# PGA257_socket.net
KiCad netlist of a schematic drawn in EAGLE
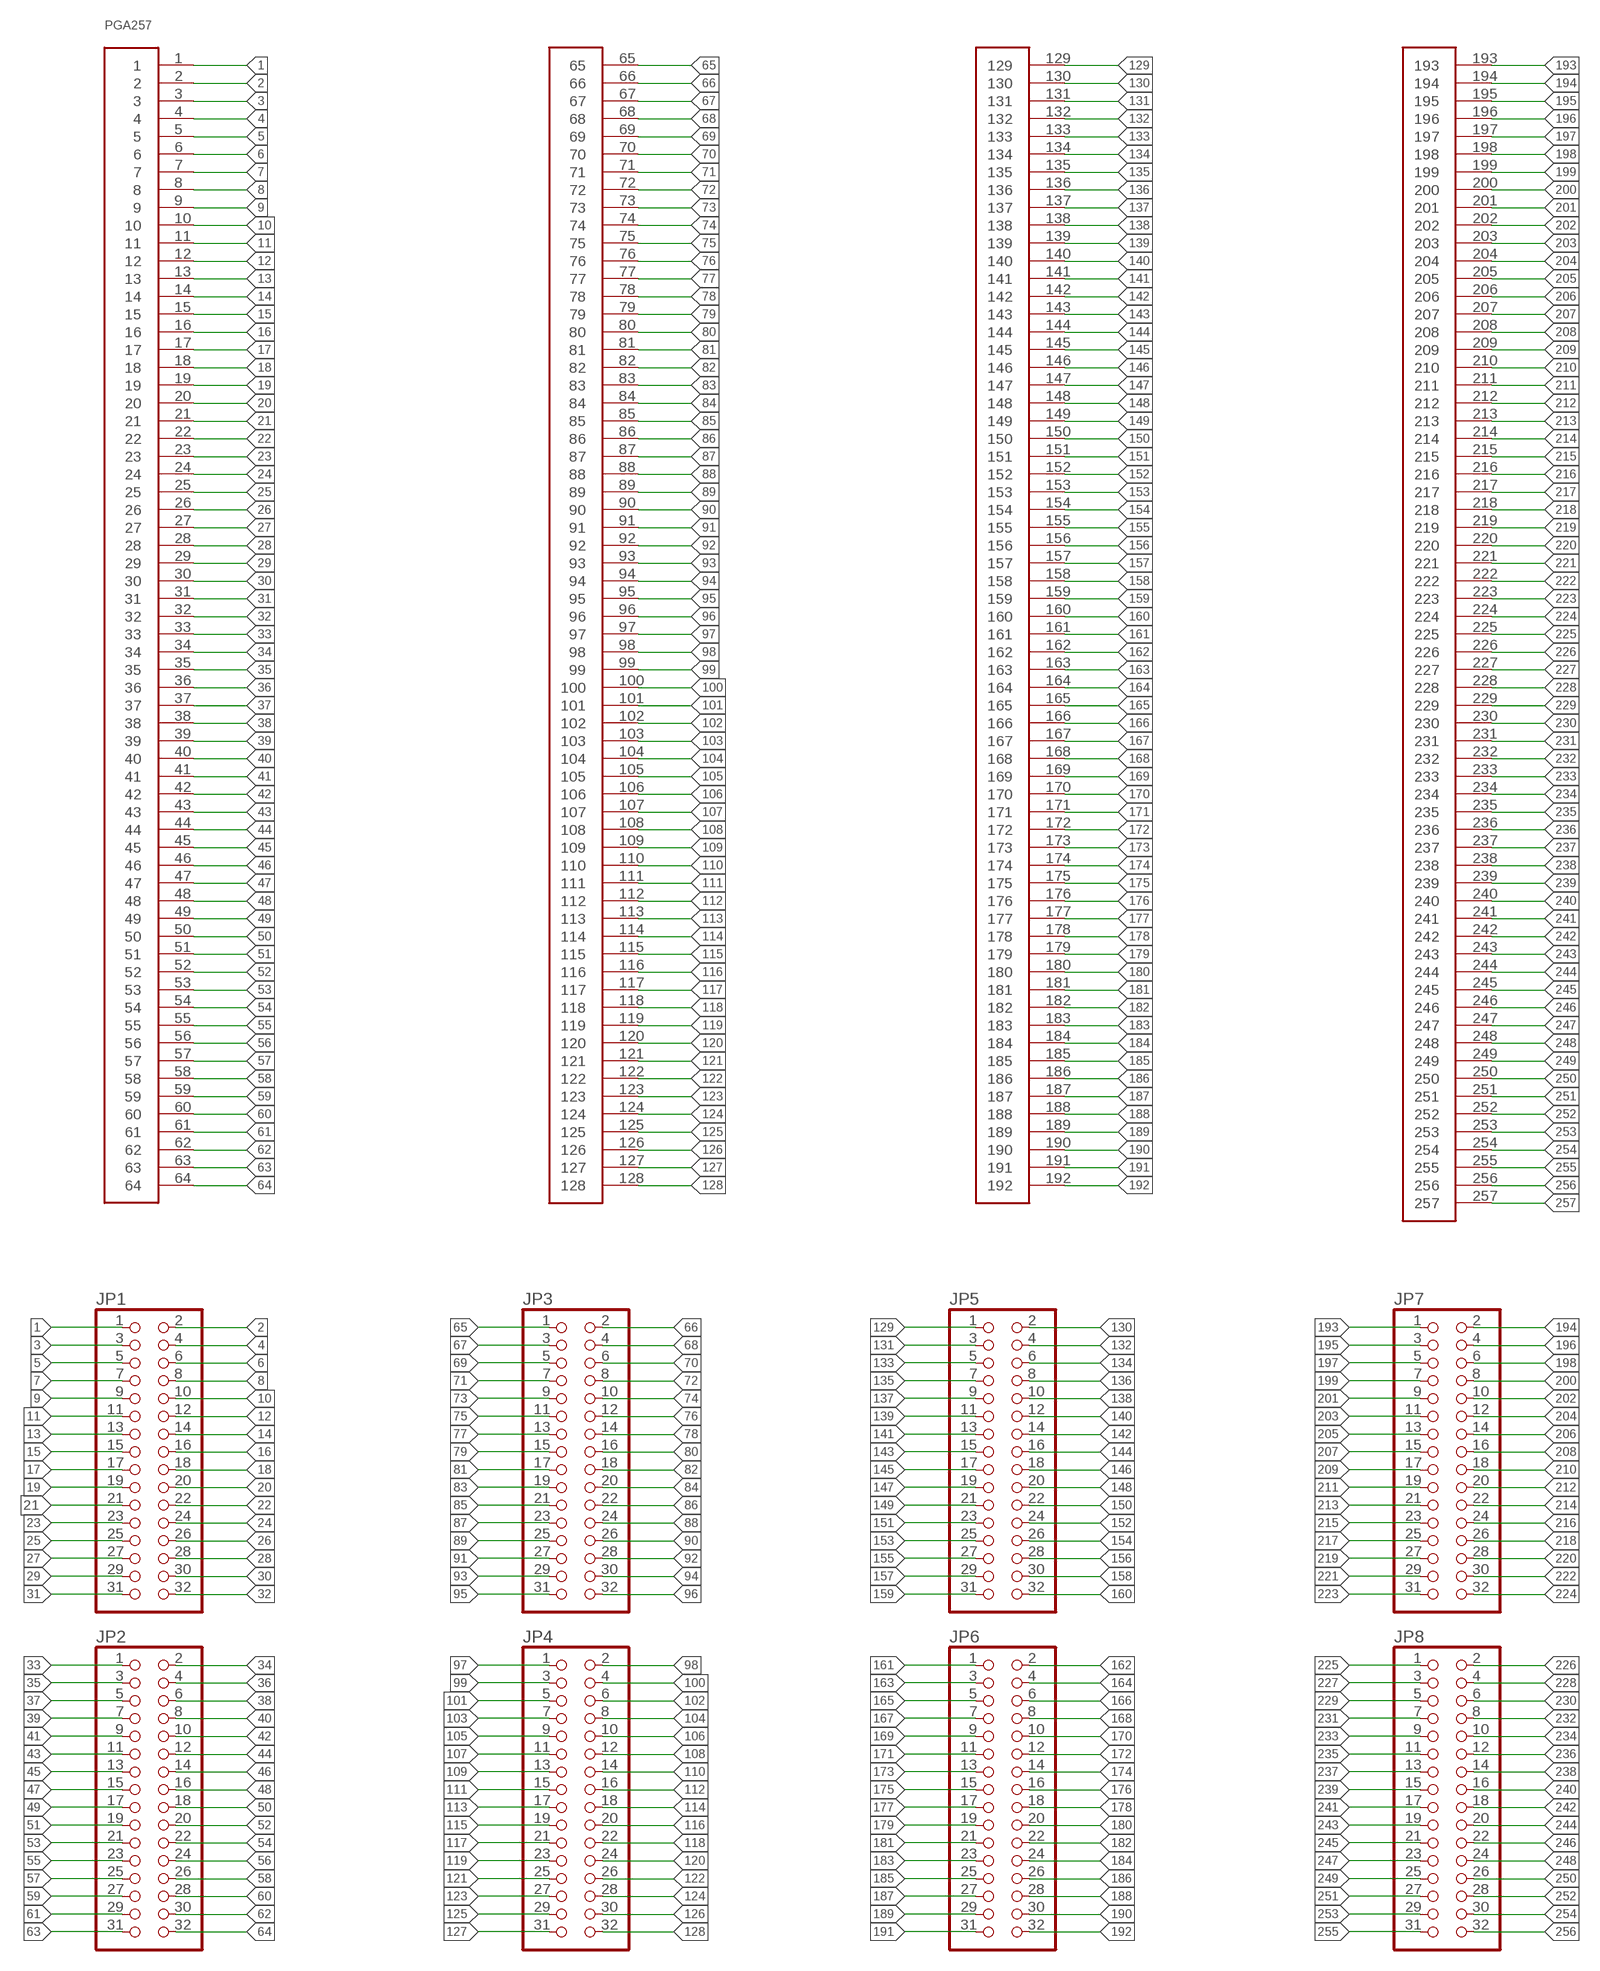
[diagram p0: schematic, sheet 1]

(export (version "E")
  (design (tool "Eeschema 10.0.6"))
  (components
    (comp (ref "JP1")
      (value "PINHD-2X16")
      (footprint "eagle-import:2X16")
      (libsource (lib "eagle-import") (part "PINHD-2X16"))
    )
    (comp (ref "JP2")
      (value "PINHD-2X16")
      (footprint "eagle-import:2X16")
      (libsource (lib "eagle-import") (part "PINHD-2X16"))
    )
    (comp (ref "JP3")
      (value "PINHD-2X16")
      (footprint "eagle-import:2X16")
      (libsource (lib "eagle-import") (part "PINHD-2X16"))
    )
    (comp (ref "JP4")
      (value "PINHD-2X16")
      (footprint "eagle-import:2X16")
      (libsource (lib "eagle-import") (part "PINHD-2X16"))
    )
    (comp (ref "JP5")
      (value "PINHD-2X16")
      (footprint "eagle-import:2X16")
      (libsource (lib "eagle-import") (part "PINHD-2X16"))
    )
    (comp (ref "JP6")
      (value "PINHD-2X16")
      (footprint "eagle-import:2X16")
      (libsource (lib "eagle-import") (part "PINHD-2X16"))
    )
    (comp (ref "JP7")
      (value "PINHD-2X16")
      (footprint "eagle-import:2X16")
      (libsource (lib "eagle-import") (part "PINHD-2X16"))
    )
    (comp (ref "JP8")
      (value "PINHD-2X16")
      (footprint "eagle-import:2X16")
      (libsource (lib "eagle-import") (part "PINHD-2X16"))
    )
    (comp (ref "PGA257")
      (value "PGA257")
      (footprint "eagle-import:PGA257")
      (libsource (lib "eagle-import") (part "PGA257"))
    )
  )
  (nets
    (net (code "1") (name "1") (class "Default")
      (node (ref "JP1") (pin "1") (pinfunction "1_1") (pintype "passive"))
      (node (ref "PGA257") (pin "1") (pinfunction "1_1") (pintype "bidirectional"))
    )
    (net (code "2") (name "2") (class "Default")
      (node (ref "JP1") (pin "2") (pinfunction "2_2") (pintype "passive"))
      (node (ref "PGA257") (pin "2") (pinfunction "2_2") (pintype "bidirectional"))
    )
    (net (code "3") (name "3") (class "Default")
      (node (ref "JP1") (pin "3") (pinfunction "3_3") (pintype "passive"))
      (node (ref "PGA257") (pin "3") (pinfunction "3_3") (pintype "bidirectional"))
    )
    (net (code "4") (name "4") (class "Default")
      (node (ref "JP1") (pin "4") (pinfunction "4_4") (pintype "passive"))
      (node (ref "PGA257") (pin "4") (pinfunction "4_4") (pintype "bidirectional"))
    )
    (net (code "5") (name "5") (class "Default")
      (node (ref "JP1") (pin "5") (pinfunction "5_5") (pintype "passive"))
      (node (ref "PGA257") (pin "5") (pinfunction "5_5") (pintype "bidirectional"))
    )
    (net (code "6") (name "6") (class "Default")
      (node (ref "JP1") (pin "6") (pinfunction "6_6") (pintype "passive"))
      (node (ref "PGA257") (pin "6") (pinfunction "6_6") (pintype "bidirectional"))
    )
    (net (code "7") (name "7") (class "Default")
      (node (ref "JP1") (pin "7") (pinfunction "7_7") (pintype "passive"))
      (node (ref "PGA257") (pin "7") (pinfunction "7_7") (pintype "bidirectional"))
    )
    (net (code "8") (name "8") (class "Default")
      (node (ref "JP1") (pin "8") (pinfunction "8_8") (pintype "passive"))
      (node (ref "PGA257") (pin "8") (pinfunction "8_8") (pintype "bidirectional"))
    )
    (net (code "9") (name "9") (class "Default")
      (node (ref "JP1") (pin "9") (pinfunction "9_9") (pintype "passive"))
      (node (ref "PGA257") (pin "9") (pinfunction "9_9") (pintype "bidirectional"))
    )
    (net (code "10") (name "10") (class "Default")
      (node (ref "JP1") (pin "10") (pinfunction "10_10") (pintype "passive"))
      (node (ref "PGA257") (pin "10") (pinfunction "10_10") (pintype "bidirectional"))
    )
    (net (code "11") (name "11") (class "Default")
      (node (ref "JP1") (pin "11") (pinfunction "11_11") (pintype "passive"))
      (node (ref "PGA257") (pin "11") (pinfunction "11_11") (pintype "bidirectional"))
    )
    (net (code "12") (name "12") (class "Default")
      (node (ref "JP1") (pin "12") (pinfunction "12_12") (pintype "passive"))
      (node (ref "PGA257") (pin "12") (pinfunction "12_12") (pintype "bidirectional"))
    )
    (net (code "13") (name "13") (class "Default")
      (node (ref "JP1") (pin "13") (pinfunction "13_13") (pintype "passive"))
      (node (ref "PGA257") (pin "13") (pinfunction "13_13") (pintype "bidirectional"))
    )
    (net (code "14") (name "14") (class "Default")
      (node (ref "JP1") (pin "14") (pinfunction "14_14") (pintype "passive"))
      (node (ref "PGA257") (pin "14") (pinfunction "14_14") (pintype "bidirectional"))
    )
    (net (code "15") (name "15") (class "Default")
      (node (ref "JP1") (pin "15") (pinfunction "15_15") (pintype "passive"))
      (node (ref "PGA257") (pin "15") (pinfunction "15_15") (pintype "bidirectional"))
    )
    (net (code "16") (name "16") (class "Default")
      (node (ref "JP1") (pin "16") (pinfunction "16_16") (pintype "passive"))
      (node (ref "PGA257") (pin "16") (pinfunction "16_16") (pintype "bidirectional"))
    )
    (net (code "17") (name "17") (class "Default")
      (node (ref "JP1") (pin "17") (pinfunction "17_17") (pintype "passive"))
      (node (ref "PGA257") (pin "17") (pinfunction "17_17") (pintype "bidirectional"))
    )
    (net (code "18") (name "18") (class "Default")
      (node (ref "JP1") (pin "18") (pinfunction "18_18") (pintype "passive"))
      (node (ref "PGA257") (pin "18") (pinfunction "18_18") (pintype "bidirectional"))
    )
    (net (code "19") (name "19") (class "Default")
      (node (ref "JP1") (pin "19") (pinfunction "19_19") (pintype "passive"))
      (node (ref "PGA257") (pin "19") (pinfunction "19_19") (pintype "bidirectional"))
    )
    (net (code "20") (name "20") (class "Default")
      (node (ref "JP1") (pin "20") (pinfunction "20_20") (pintype "passive"))
      (node (ref "PGA257") (pin "20") (pinfunction "20_20") (pintype "bidirectional"))
    )
    (net (code "21") (name "21") (class "Default")
      (node (ref "JP1") (pin "21") (pinfunction "21_21") (pintype "passive"))
      (node (ref "PGA257") (pin "21") (pinfunction "21_21") (pintype "bidirectional"))
    )
    (net (code "22") (name "22") (class "Default")
      (node (ref "JP1") (pin "22") (pinfunction "22_22") (pintype "passive"))
      (node (ref "PGA257") (pin "22") (pinfunction "22_22") (pintype "bidirectional"))
    )
    (net (code "23") (name "23") (class "Default")
      (node (ref "JP1") (pin "23") (pinfunction "23_23") (pintype "passive"))
      (node (ref "PGA257") (pin "23") (pinfunction "23_23") (pintype "bidirectional"))
    )
    (net (code "24") (name "24") (class "Default")
      (node (ref "JP1") (pin "24") (pinfunction "24_24") (pintype "passive"))
      (node (ref "PGA257") (pin "24") (pinfunction "24_24") (pintype "bidirectional"))
    )
    (net (code "25") (name "25") (class "Default")
      (node (ref "JP1") (pin "25") (pinfunction "25_25") (pintype "passive"))
      (node (ref "PGA257") (pin "25") (pinfunction "25_25") (pintype "bidirectional"))
    )
    (net (code "26") (name "26") (class "Default")
      (node (ref "JP1") (pin "26") (pinfunction "26_26") (pintype "passive"))
      (node (ref "PGA257") (pin "26") (pinfunction "26_26") (pintype "bidirectional"))
    )
    (net (code "27") (name "27") (class "Default")
      (node (ref "JP1") (pin "27") (pinfunction "27_27") (pintype "passive"))
      (node (ref "PGA257") (pin "27") (pinfunction "27_27") (pintype "bidirectional"))
    )
    (net (code "28") (name "28") (class "Default")
      (node (ref "JP1") (pin "28") (pinfunction "28_28") (pintype "passive"))
      (node (ref "PGA257") (pin "28") (pinfunction "28_28") (pintype "bidirectional"))
    )
    (net (code "29") (name "29") (class "Default")
      (node (ref "JP1") (pin "29") (pinfunction "29_29") (pintype "passive"))
      (node (ref "PGA257") (pin "29") (pinfunction "29_29") (pintype "bidirectional"))
    )
    (net (code "30") (name "30") (class "Default")
      (node (ref "JP1") (pin "30") (pinfunction "30_30") (pintype "passive"))
      (node (ref "PGA257") (pin "30") (pinfunction "30_30") (pintype "bidirectional"))
    )
    (net (code "31") (name "31") (class "Default")
      (node (ref "JP1") (pin "31") (pinfunction "31_31") (pintype "passive"))
      (node (ref "PGA257") (pin "31") (pinfunction "31_31") (pintype "bidirectional"))
    )
    (net (code "32") (name "32") (class "Default")
      (node (ref "JP1") (pin "32") (pinfunction "32_32") (pintype "passive"))
      (node (ref "PGA257") (pin "32") (pinfunction "32_32") (pintype "bidirectional"))
    )
    (net (code "33") (name "33") (class "Default")
      (node (ref "JP2") (pin "1") (pinfunction "1_1") (pintype "passive"))
      (node (ref "PGA257") (pin "33") (pinfunction "33_33") (pintype "bidirectional"))
    )
    (net (code "34") (name "34") (class "Default")
      (node (ref "JP2") (pin "2") (pinfunction "2_2") (pintype "passive"))
      (node (ref "PGA257") (pin "34") (pinfunction "34_34") (pintype "bidirectional"))
    )
    (net (code "35") (name "35") (class "Default")
      (node (ref "JP2") (pin "3") (pinfunction "3_3") (pintype "passive"))
      (node (ref "PGA257") (pin "35") (pinfunction "35_35") (pintype "bidirectional"))
    )
    (net (code "36") (name "36") (class "Default")
      (node (ref "JP2") (pin "4") (pinfunction "4_4") (pintype "passive"))
      (node (ref "PGA257") (pin "36") (pinfunction "36_36") (pintype "bidirectional"))
    )
    (net (code "37") (name "37") (class "Default")
      (node (ref "JP2") (pin "5") (pinfunction "5_5") (pintype "passive"))
      (node (ref "PGA257") (pin "37") (pinfunction "37_37") (pintype "bidirectional"))
    )
    (net (code "38") (name "38") (class "Default")
      (node (ref "JP2") (pin "6") (pinfunction "6_6") (pintype "passive"))
      (node (ref "PGA257") (pin "38") (pinfunction "38_38") (pintype "bidirectional"))
    )
    (net (code "39") (name "39") (class "Default")
      (node (ref "JP2") (pin "7") (pinfunction "7_7") (pintype "passive"))
      (node (ref "PGA257") (pin "39") (pinfunction "39_39") (pintype "bidirectional"))
    )
    (net (code "40") (name "40") (class "Default")
      (node (ref "JP2") (pin "8") (pinfunction "8_8") (pintype "passive"))
      (node (ref "PGA257") (pin "40") (pinfunction "40_40") (pintype "bidirectional"))
    )
    (net (code "41") (name "41") (class "Default")
      (node (ref "JP2") (pin "9") (pinfunction "9_9") (pintype "passive"))
      (node (ref "PGA257") (pin "41") (pinfunction "41_41") (pintype "bidirectional"))
    )
    (net (code "42") (name "42") (class "Default")
      (node (ref "JP2") (pin "10") (pinfunction "10_10") (pintype "passive"))
      (node (ref "PGA257") (pin "42") (pinfunction "42_42") (pintype "bidirectional"))
    )
    (net (code "43") (name "43") (class "Default")
      (node (ref "JP2") (pin "11") (pinfunction "11_11") (pintype "passive"))
      (node (ref "PGA257") (pin "43") (pinfunction "43_43") (pintype "bidirectional"))
    )
    (net (code "44") (name "44") (class "Default")
      (node (ref "JP2") (pin "12") (pinfunction "12_12") (pintype "passive"))
      (node (ref "PGA257") (pin "44") (pinfunction "44_44") (pintype "bidirectional"))
    )
    (net (code "45") (name "45") (class "Default")
      (node (ref "JP2") (pin "13") (pinfunction "13_13") (pintype "passive"))
      (node (ref "PGA257") (pin "45") (pinfunction "45_45") (pintype "bidirectional"))
    )
    (net (code "46") (name "46") (class "Default")
      (node (ref "JP2") (pin "14") (pinfunction "14_14") (pintype "passive"))
      (node (ref "PGA257") (pin "46") (pinfunction "46_46") (pintype "bidirectional"))
    )
    (net (code "47") (name "47") (class "Default")
      (node (ref "JP2") (pin "15") (pinfunction "15_15") (pintype "passive"))
      (node (ref "PGA257") (pin "47") (pinfunction "47_47") (pintype "bidirectional"))
    )
    (net (code "48") (name "48") (class "Default")
      (node (ref "JP2") (pin "16") (pinfunction "16_16") (pintype "passive"))
      (node (ref "PGA257") (pin "48") (pinfunction "48_48") (pintype "bidirectional"))
    )
    (net (code "49") (name "49") (class "Default")
      (node (ref "JP2") (pin "17") (pinfunction "17_17") (pintype "passive"))
      (node (ref "PGA257") (pin "49") (pinfunction "49_49") (pintype "bidirectional"))
    )
    (net (code "50") (name "50") (class "Default")
      (node (ref "JP2") (pin "18") (pinfunction "18_18") (pintype "passive"))
      (node (ref "PGA257") (pin "50") (pinfunction "50_50") (pintype "bidirectional"))
    )
    (net (code "51") (name "51") (class "Default")
      (node (ref "JP2") (pin "19") (pinfunction "19_19") (pintype "passive"))
      (node (ref "PGA257") (pin "51") (pinfunction "51_51") (pintype "bidirectional"))
    )
    (net (code "52") (name "52") (class "Default")
      (node (ref "JP2") (pin "20") (pinfunction "20_20") (pintype "passive"))
      (node (ref "PGA257") (pin "52") (pinfunction "52_52") (pintype "bidirectional"))
    )
    (net (code "53") (name "53") (class "Default")
      (node (ref "JP2") (pin "21") (pinfunction "21_21") (pintype "passive"))
      (node (ref "PGA257") (pin "53") (pinfunction "53_53") (pintype "bidirectional"))
    )
    (net (code "54") (name "54") (class "Default")
      (node (ref "JP2") (pin "22") (pinfunction "22_22") (pintype "passive"))
      (node (ref "PGA257") (pin "54") (pinfunction "54_54") (pintype "bidirectional"))
    )
    (net (code "55") (name "55") (class "Default")
      (node (ref "JP2") (pin "23") (pinfunction "23_23") (pintype "passive"))
      (node (ref "PGA257") (pin "55") (pinfunction "55_55") (pintype "bidirectional"))
    )
    (net (code "56") (name "56") (class "Default")
      (node (ref "JP2") (pin "24") (pinfunction "24_24") (pintype "passive"))
      (node (ref "PGA257") (pin "56") (pinfunction "56_56") (pintype "bidirectional"))
    )
    (net (code "57") (name "57") (class "Default")
      (node (ref "JP2") (pin "25") (pinfunction "25_25") (pintype "passive"))
      (node (ref "PGA257") (pin "57") (pinfunction "57_57") (pintype "bidirectional"))
    )
    (net (code "58") (name "58") (class "Default")
      (node (ref "JP2") (pin "26") (pinfunction "26_26") (pintype "passive"))
      (node (ref "PGA257") (pin "58") (pinfunction "58_58") (pintype "bidirectional"))
    )
    (net (code "59") (name "59") (class "Default")
      (node (ref "JP2") (pin "27") (pinfunction "27_27") (pintype "passive"))
      (node (ref "PGA257") (pin "59") (pinfunction "59_59") (pintype "bidirectional"))
    )
    (net (code "60") (name "60") (class "Default")
      (node (ref "JP2") (pin "28") (pinfunction "28_28") (pintype "passive"))
      (node (ref "PGA257") (pin "60") (pinfunction "60_60") (pintype "bidirectional"))
    )
    (net (code "61") (name "61") (class "Default")
      (node (ref "JP2") (pin "29") (pinfunction "29_29") (pintype "passive"))
      (node (ref "PGA257") (pin "61") (pinfunction "61_61") (pintype "bidirectional"))
    )
    (net (code "62") (name "62") (class "Default")
      (node (ref "JP2") (pin "30") (pinfunction "30_30") (pintype "passive"))
      (node (ref "PGA257") (pin "62") (pinfunction "62_62") (pintype "bidirectional"))
    )
    (net (code "63") (name "63") (class "Default")
      (node (ref "JP2") (pin "31") (pinfunction "31_31") (pintype "passive"))
      (node (ref "PGA257") (pin "63") (pinfunction "63_63") (pintype "bidirectional"))
    )
    (net (code "64") (name "64") (class "Default")
      (node (ref "JP2") (pin "32") (pinfunction "32_32") (pintype "passive"))
      (node (ref "PGA257") (pin "64") (pinfunction "64_64") (pintype "bidirectional"))
    )
    (net (code "65") (name "65") (class "Default")
      (node (ref "JP3") (pin "1") (pinfunction "1_1") (pintype "passive"))
      (node (ref "PGA257") (pin "65") (pinfunction "65_65") (pintype "bidirectional"))
    )
    (net (code "66") (name "66") (class "Default")
      (node (ref "JP3") (pin "2") (pinfunction "2_2") (pintype "passive"))
      (node (ref "PGA257") (pin "66") (pinfunction "66_66") (pintype "bidirectional"))
    )
    (net (code "67") (name "67") (class "Default")
      (node (ref "JP3") (pin "3") (pinfunction "3_3") (pintype "passive"))
      (node (ref "PGA257") (pin "67") (pinfunction "67_67") (pintype "bidirectional"))
    )
    (net (code "68") (name "68") (class "Default")
      (node (ref "JP3") (pin "4") (pinfunction "4_4") (pintype "passive"))
      (node (ref "PGA257") (pin "68") (pinfunction "68_68") (pintype "bidirectional"))
    )
    (net (code "69") (name "69") (class "Default")
      (node (ref "JP3") (pin "5") (pinfunction "5_5") (pintype "passive"))
      (node (ref "PGA257") (pin "69") (pinfunction "69_69") (pintype "bidirectional"))
    )
    (net (code "70") (name "70") (class "Default")
      (node (ref "JP3") (pin "6") (pinfunction "6_6") (pintype "passive"))
      (node (ref "PGA257") (pin "70") (pinfunction "70_70") (pintype "bidirectional"))
    )
    (net (code "71") (name "71") (class "Default")
      (node (ref "JP3") (pin "7") (pinfunction "7_7") (pintype "passive"))
      (node (ref "PGA257") (pin "71") (pinfunction "71_71") (pintype "bidirectional"))
    )
    (net (code "72") (name "72") (class "Default")
      (node (ref "JP3") (pin "8") (pinfunction "8_8") (pintype "passive"))
      (node (ref "PGA257") (pin "72") (pinfunction "72_72") (pintype "bidirectional"))
    )
    (net (code "73") (name "73") (class "Default")
      (node (ref "JP3") (pin "9") (pinfunction "9_9") (pintype "passive"))
      (node (ref "PGA257") (pin "73") (pinfunction "73_73") (pintype "bidirectional"))
    )
    (net (code "74") (name "74") (class "Default")
      (node (ref "JP3") (pin "10") (pinfunction "10_10") (pintype "passive"))
      (node (ref "PGA257") (pin "74") (pinfunction "74_74") (pintype "bidirectional"))
    )
    (net (code "75") (name "75") (class "Default")
      (node (ref "JP3") (pin "11") (pinfunction "11_11") (pintype "passive"))
      (node (ref "PGA257") (pin "75") (pinfunction "75_75") (pintype "bidirectional"))
    )
    (net (code "76") (name "76") (class "Default")
      (node (ref "JP3") (pin "12") (pinfunction "12_12") (pintype "passive"))
      (node (ref "PGA257") (pin "76") (pinfunction "76_76") (pintype "bidirectional"))
    )
    (net (code "77") (name "77") (class "Default")
      (node (ref "JP3") (pin "13") (pinfunction "13_13") (pintype "passive"))
      (node (ref "PGA257") (pin "77") (pinfunction "77_77") (pintype "bidirectional"))
    )
    (net (code "78") (name "78") (class "Default")
      (node (ref "JP3") (pin "14") (pinfunction "14_14") (pintype "passive"))
      (node (ref "PGA257") (pin "78") (pinfunction "78_78") (pintype "bidirectional"))
    )
    (net (code "79") (name "79") (class "Default")
      (node (ref "JP3") (pin "15") (pinfunction "15_15") (pintype "passive"))
      (node (ref "PGA257") (pin "79") (pinfunction "79_79") (pintype "bidirectional"))
    )
    (net (code "80") (name "80") (class "Default")
      (node (ref "JP3") (pin "16") (pinfunction "16_16") (pintype "passive"))
      (node (ref "PGA257") (pin "80") (pinfunction "80_80") (pintype "bidirectional"))
    )
    (net (code "81") (name "81") (class "Default")
      (node (ref "JP3") (pin "17") (pinfunction "17_17") (pintype "passive"))
      (node (ref "PGA257") (pin "81") (pinfunction "81_81") (pintype "bidirectional"))
    )
    (net (code "82") (name "82") (class "Default")
      (node (ref "JP3") (pin "18") (pinfunction "18_18") (pintype "passive"))
      (node (ref "PGA257") (pin "82") (pinfunction "82_82") (pintype "bidirectional"))
    )
    (net (code "83") (name "83") (class "Default")
      (node (ref "JP3") (pin "19") (pinfunction "19_19") (pintype "passive"))
      (node (ref "PGA257") (pin "83") (pinfunction "83_83") (pintype "bidirectional"))
    )
    (net (code "84") (name "84") (class "Default")
      (node (ref "JP3") (pin "20") (pinfunction "20_20") (pintype "passive"))
      (node (ref "PGA257") (pin "84") (pinfunction "84_84") (pintype "bidirectional"))
    )
    (net (code "85") (name "85") (class "Default")
      (node (ref "JP3") (pin "21") (pinfunction "21_21") (pintype "passive"))
      (node (ref "PGA257") (pin "85") (pinfunction "85_85") (pintype "bidirectional"))
    )
    (net (code "86") (name "86") (class "Default")
      (node (ref "JP3") (pin "22") (pinfunction "22_22") (pintype "passive"))
      (node (ref "PGA257") (pin "86") (pinfunction "86_86") (pintype "bidirectional"))
    )
    (net (code "87") (name "87") (class "Default")
      (node (ref "JP3") (pin "23") (pinfunction "23_23") (pintype "passive"))
      (node (ref "PGA257") (pin "87") (pinfunction "87_87") (pintype "bidirectional"))
    )
    (net (code "88") (name "88") (class "Default")
      (node (ref "JP3") (pin "24") (pinfunction "24_24") (pintype "passive"))
      (node (ref "PGA257") (pin "88") (pinfunction "88_88") (pintype "bidirectional"))
    )
    (net (code "89") (name "89") (class "Default")
      (node (ref "JP3") (pin "25") (pinfunction "25_25") (pintype "passive"))
      (node (ref "PGA257") (pin "89") (pinfunction "89_89") (pintype "bidirectional"))
    )
    (net (code "90") (name "90") (class "Default")
      (node (ref "JP3") (pin "26") (pinfunction "26_26") (pintype "passive"))
      (node (ref "PGA257") (pin "90") (pinfunction "90_90") (pintype "bidirectional"))
    )
    (net (code "91") (name "91") (class "Default")
      (node (ref "JP3") (pin "27") (pinfunction "27_27") (pintype "passive"))
      (node (ref "PGA257") (pin "91") (pinfunction "91_91") (pintype "bidirectional"))
    )
    (net (code "92") (name "92") (class "Default")
      (node (ref "JP3") (pin "28") (pinfunction "28_28") (pintype "passive"))
      (node (ref "PGA257") (pin "92") (pinfunction "92_92") (pintype "bidirectional"))
    )
    (net (code "93") (name "93") (class "Default")
      (node (ref "JP3") (pin "29") (pinfunction "29_29") (pintype "passive"))
      (node (ref "PGA257") (pin "93") (pinfunction "93_93") (pintype "bidirectional"))
    )
    (net (code "94") (name "94") (class "Default")
      (node (ref "JP3") (pin "30") (pinfunction "30_30") (pintype "passive"))
      (node (ref "PGA257") (pin "94") (pinfunction "94_94") (pintype "bidirectional"))
    )
    (net (code "95") (name "95") (class "Default")
      (node (ref "JP3") (pin "31") (pinfunction "31_31") (pintype "passive"))
      (node (ref "PGA257") (pin "95") (pinfunction "95_95") (pintype "bidirectional"))
    )
    (net (code "96") (name "96") (class "Default")
      (node (ref "JP3") (pin "32") (pinfunction "32_32") (pintype "passive"))
      (node (ref "PGA257") (pin "96") (pinfunction "96_96") (pintype "bidirectional"))
    )
    (net (code "97") (name "97") (class "Default")
      (node (ref "JP4") (pin "1") (pinfunction "1_1") (pintype "passive"))
      (node (ref "PGA257") (pin "97") (pinfunction "97_97") (pintype "bidirectional"))
    )
    (net (code "98") (name "98") (class "Default")
      (node (ref "JP4") (pin "2") (pinfunction "2_2") (pintype "passive"))
      (node (ref "PGA257") (pin "98") (pinfunction "98_98") (pintype "bidirectional"))
    )
    (net (code "99") (name "99") (class "Default")
      (node (ref "JP4") (pin "3") (pinfunction "3_3") (pintype "passive"))
      (node (ref "PGA257") (pin "99") (pinfunction "99_99") (pintype "bidirectional"))
    )
    (net (code "100") (name "100") (class "Default")
      (node (ref "JP4") (pin "4") (pinfunction "4_4") (pintype "passive"))
      (node (ref "PGA257") (pin "100") (pinfunction "100_100") (pintype "bidirectional"))
    )
    (net (code "101") (name "101") (class "Default")
      (node (ref "JP4") (pin "5") (pinfunction "5_5") (pintype "passive"))
      (node (ref "PGA257") (pin "101") (pinfunction "101_101") (pintype "bidirectional"))
    )
    (net (code "102") (name "102") (class "Default")
      (node (ref "JP4") (pin "6") (pinfunction "6_6") (pintype "passive"))
      (node (ref "PGA257") (pin "102") (pinfunction "102_102") (pintype "bidirectional"))
    )
    (net (code "103") (name "103") (class "Default")
      (node (ref "JP4") (pin "7") (pinfunction "7_7") (pintype "passive"))
      (node (ref "PGA257") (pin "103") (pinfunction "103_103") (pintype "bidirectional"))
    )
    (net (code "104") (name "104") (class "Default")
      (node (ref "JP4") (pin "8") (pinfunction "8_8") (pintype "passive"))
      (node (ref "PGA257") (pin "104") (pinfunction "104_104") (pintype "bidirectional"))
    )
    (net (code "105") (name "105") (class "Default")
      (node (ref "JP4") (pin "9") (pinfunction "9_9") (pintype "passive"))
      (node (ref "PGA257") (pin "105") (pinfunction "105_105") (pintype "bidirectional"))
    )
    (net (code "106") (name "106") (class "Default")
      (node (ref "JP4") (pin "10") (pinfunction "10_10") (pintype "passive"))
      (node (ref "PGA257") (pin "106") (pinfunction "106_106") (pintype "bidirectional"))
    )
    (net (code "107") (name "107") (class "Default")
      (node (ref "JP4") (pin "11") (pinfunction "11_11") (pintype "passive"))
      (node (ref "PGA257") (pin "107") (pinfunction "107_107") (pintype "bidirectional"))
    )
    (net (code "108") (name "108") (class "Default")
      (node (ref "JP4") (pin "12") (pinfunction "12_12") (pintype "passive"))
      (node (ref "PGA257") (pin "108") (pinfunction "108_108") (pintype "bidirectional"))
    )
    (net (code "109") (name "109") (class "Default")
      (node (ref "JP4") (pin "13") (pinfunction "13_13") (pintype "passive"))
      (node (ref "PGA257") (pin "109") (pinfunction "109_109") (pintype "bidirectional"))
    )
    (net (code "110") (name "110") (class "Default")
      (node (ref "JP4") (pin "14") (pinfunction "14_14") (pintype "passive"))
      (node (ref "PGA257") (pin "110") (pinfunction "110_110") (pintype "bidirectional"))
    )
    (net (code "111") (name "111") (class "Default")
      (node (ref "JP4") (pin "15") (pinfunction "15_15") (pintype "passive"))
      (node (ref "PGA257") (pin "111") (pinfunction "111_111") (pintype "bidirectional"))
    )
    (net (code "112") (name "112") (class "Default")
      (node (ref "JP4") (pin "16") (pinfunction "16_16") (pintype "passive"))
      (node (ref "PGA257") (pin "112") (pinfunction "112_112") (pintype "bidirectional"))
    )
    (net (code "113") (name "113") (class "Default")
      (node (ref "JP4") (pin "17") (pinfunction "17_17") (pintype "passive"))
      (node (ref "PGA257") (pin "113") (pinfunction "113_113") (pintype "bidirectional"))
    )
    (net (code "114") (name "114") (class "Default")
      (node (ref "JP4") (pin "18") (pinfunction "18_18") (pintype "passive"))
      (node (ref "PGA257") (pin "114") (pinfunction "114_114") (pintype "bidirectional"))
    )
    (net (code "115") (name "115") (class "Default")
      (node (ref "JP4") (pin "19") (pinfunction "19_19") (pintype "passive"))
      (node (ref "PGA257") (pin "115") (pinfunction "115_115") (pintype "bidirectional"))
    )
    (net (code "116") (name "116") (class "Default")
      (node (ref "JP4") (pin "20") (pinfunction "20_20") (pintype "passive"))
      (node (ref "PGA257") (pin "116") (pinfunction "116_116") (pintype "bidirectional"))
    )
    (net (code "117") (name "117") (class "Default")
      (node (ref "JP4") (pin "21") (pinfunction "21_21") (pintype "passive"))
      (node (ref "PGA257") (pin "117") (pinfunction "117_117") (pintype "bidirectional"))
    )
    (net (code "118") (name "118") (class "Default")
      (node (ref "JP4") (pin "22") (pinfunction "22_22") (pintype "passive"))
      (node (ref "PGA257") (pin "118") (pinfunction "118_118") (pintype "bidirectional"))
    )
    (net (code "119") (name "119") (class "Default")
      (node (ref "JP4") (pin "23") (pinfunction "23_23") (pintype "passive"))
      (node (ref "PGA257") (pin "119") (pinfunction "119_119") (pintype "bidirectional"))
    )
    (net (code "120") (name "120") (class "Default")
      (node (ref "JP4") (pin "24") (pinfunction "24_24") (pintype "passive"))
      (node (ref "PGA257") (pin "120") (pinfunction "120_120") (pintype "bidirectional"))
    )
    (net (code "121") (name "121") (class "Default")
      (node (ref "JP4") (pin "25") (pinfunction "25_25") (pintype "passive"))
      (node (ref "PGA257") (pin "121") (pinfunction "121_121") (pintype "bidirectional"))
    )
    (net (code "122") (name "122") (class "Default")
      (node (ref "JP4") (pin "26") (pinfunction "26_26") (pintype "passive"))
      (node (ref "PGA257") (pin "122") (pinfunction "122_122") (pintype "bidirectional"))
    )
    (net (code "123") (name "123") (class "Default")
      (node (ref "JP4") (pin "27") (pinfunction "27_27") (pintype "passive"))
      (node (ref "PGA257") (pin "123") (pinfunction "123_123") (pintype "bidirectional"))
    )
    (net (code "124") (name "124") (class "Default")
      (node (ref "JP4") (pin "28") (pinfunction "28_28") (pintype "passive"))
      (node (ref "PGA257") (pin "124") (pinfunction "124_124") (pintype "bidirectional"))
    )
    (net (code "125") (name "125") (class "Default")
      (node (ref "JP4") (pin "29") (pinfunction "29_29") (pintype "passive"))
      (node (ref "PGA257") (pin "125") (pinfunction "125_125") (pintype "bidirectional"))
    )
    (net (code "126") (name "126") (class "Default")
      (node (ref "JP4") (pin "30") (pinfunction "30_30") (pintype "passive"))
      (node (ref "PGA257") (pin "126") (pinfunction "126_126") (pintype "bidirectional"))
    )
    (net (code "127") (name "127") (class "Default")
      (node (ref "JP4") (pin "31") (pinfunction "31_31") (pintype "passive"))
      (node (ref "PGA257") (pin "127") (pinfunction "127_127") (pintype "bidirectional"))
    )
    (net (code "128") (name "128") (class "Default")
      (node (ref "JP4") (pin "32") (pinfunction "32_32") (pintype "passive"))
      (node (ref "PGA257") (pin "128") (pinfunction "128_128") (pintype "bidirectional"))
    )
    (net (code "129") (name "129") (class "Default")
      (node (ref "JP5") (pin "1") (pinfunction "1_1") (pintype "passive"))
      (node (ref "PGA257") (pin "129") (pinfunction "129_129") (pintype "bidirectional"))
    )
    (net (code "130") (name "130") (class "Default")
      (node (ref "JP5") (pin "2") (pinfunction "2_2") (pintype "passive"))
      (node (ref "PGA257") (pin "130") (pinfunction "130_130") (pintype "bidirectional"))
    )
    (net (code "131") (name "131") (class "Default")
      (node (ref "JP5") (pin "3") (pinfunction "3_3") (pintype "passive"))
      (node (ref "PGA257") (pin "131") (pinfunction "131_131") (pintype "bidirectional"))
    )
    (net (code "132") (name "132") (class "Default")
      (node (ref "JP5") (pin "4") (pinfunction "4_4") (pintype "passive"))
      (node (ref "PGA257") (pin "132") (pinfunction "132_132") (pintype "bidirectional"))
    )
    (net (code "133") (name "133") (class "Default")
      (node (ref "JP5") (pin "5") (pinfunction "5_5") (pintype "passive"))
      (node (ref "PGA257") (pin "133") (pinfunction "133_133") (pintype "bidirectional"))
    )
    (net (code "134") (name "134") (class "Default")
      (node (ref "JP5") (pin "6") (pinfunction "6_6") (pintype "passive"))
      (node (ref "PGA257") (pin "134") (pinfunction "134_134") (pintype "bidirectional"))
    )
    (net (code "135") (name "135") (class "Default")
      (node (ref "JP5") (pin "7") (pinfunction "7_7") (pintype "passive"))
      (node (ref "PGA257") (pin "135") (pinfunction "135_135") (pintype "bidirectional"))
    )
    (net (code "136") (name "136") (class "Default")
      (node (ref "JP5") (pin "8") (pinfunction "8_8") (pintype "passive"))
      (node (ref "PGA257") (pin "136") (pinfunction "136_136") (pintype "bidirectional"))
    )
    (net (code "137") (name "137") (class "Default")
      (node (ref "JP5") (pin "9") (pinfunction "9_9") (pintype "passive"))
      (node (ref "PGA257") (pin "137") (pinfunction "137_137") (pintype "bidirectional"))
    )
    (net (code "138") (name "138") (class "Default")
      (node (ref "JP5") (pin "10") (pinfunction "10_10") (pintype "passive"))
      (node (ref "PGA257") (pin "138") (pinfunction "138_138") (pintype "bidirectional"))
    )
    (net (code "139") (name "139") (class "Default")
      (node (ref "JP5") (pin "11") (pinfunction "11_11") (pintype "passive"))
      (node (ref "PGA257") (pin "139") (pinfunction "139_139") (pintype "bidirectional"))
    )
    (net (code "140") (name "140") (class "Default")
      (node (ref "JP5") (pin "12") (pinfunction "12_12") (pintype "passive"))
      (node (ref "PGA257") (pin "140") (pinfunction "140_140") (pintype "bidirectional"))
    )
    (net (code "141") (name "141") (class "Default")
      (node (ref "JP5") (pin "13") (pinfunction "13_13") (pintype "passive"))
      (node (ref "PGA257") (pin "141") (pinfunction "141_141") (pintype "bidirectional"))
    )
    (net (code "142") (name "142") (class "Default")
      (node (ref "JP5") (pin "14") (pinfunction "14_14") (pintype "passive"))
      (node (ref "PGA257") (pin "142") (pinfunction "142_142") (pintype "bidirectional"))
    )
    (net (code "143") (name "143") (class "Default")
      (node (ref "JP5") (pin "15") (pinfunction "15_15") (pintype "passive"))
      (node (ref "PGA257") (pin "143") (pinfunction "143_143") (pintype "bidirectional"))
    )
    (net (code "144") (name "144") (class "Default")
      (node (ref "JP5") (pin "16") (pinfunction "16_16") (pintype "passive"))
      (node (ref "PGA257") (pin "144") (pinfunction "144_144") (pintype "bidirectional"))
    )
    (net (code "145") (name "145") (class "Default")
      (node (ref "JP5") (pin "17") (pinfunction "17_17") (pintype "passive"))
      (node (ref "PGA257") (pin "145") (pinfunction "145_145") (pintype "bidirectional"))
    )
    (net (code "146") (name "146") (class "Default")
      (node (ref "JP5") (pin "18") (pinfunction "18_18") (pintype "passive"))
      (node (ref "PGA257") (pin "146") (pinfunction "146_146") (pintype "bidirectional"))
    )
    (net (code "147") (name "147") (class "Default")
      (node (ref "JP5") (pin "19") (pinfunction "19_19") (pintype "passive"))
      (node (ref "PGA257") (pin "147") (pinfunction "147_147") (pintype "bidirectional"))
    )
    (net (code "148") (name "148") (class "Default")
      (node (ref "JP5") (pin "20") (pinfunction "20_20") (pintype "passive"))
      (node (ref "PGA257") (pin "148") (pinfunction "148_148") (pintype "bidirectional"))
    )
    (net (code "149") (name "149") (class "Default")
      (node (ref "JP5") (pin "21") (pinfunction "21_21") (pintype "passive"))
      (node (ref "PGA257") (pin "149") (pinfunction "149_149") (pintype "bidirectional"))
    )
    (net (code "150") (name "150") (class "Default")
      (node (ref "JP5") (pin "22") (pinfunction "22_22") (pintype "passive"))
      (node (ref "PGA257") (pin "150") (pinfunction "150_150") (pintype "bidirectional"))
    )
    (net (code "151") (name "151") (class "Default")
      (node (ref "JP5") (pin "23") (pinfunction "23_23") (pintype "passive"))
      (node (ref "PGA257") (pin "151") (pinfunction "151_151") (pintype "bidirectional"))
    )
    (net (code "152") (name "152") (class "Default")
      (node (ref "JP5") (pin "24") (pinfunction "24_24") (pintype "passive"))
      (node (ref "PGA257") (pin "152") (pinfunction "152_152") (pintype "bidirectional"))
    )
    (net (code "153") (name "153") (class "Default")
      (node (ref "JP5") (pin "25") (pinfunction "25_25") (pintype "passive"))
      (node (ref "PGA257") (pin "153") (pinfunction "153_153") (pintype "bidirectional"))
    )
    (net (code "154") (name "154") (class "Default")
      (node (ref "JP5") (pin "26") (pinfunction "26_26") (pintype "passive"))
      (node (ref "PGA257") (pin "154") (pinfunction "154_154") (pintype "bidirectional"))
    )
    (net (code "155") (name "155") (class "Default")
      (node (ref "JP5") (pin "27") (pinfunction "27_27") (pintype "passive"))
      (node (ref "PGA257") (pin "155") (pinfunction "155_155") (pintype "bidirectional"))
    )
    (net (code "156") (name "156") (class "Default")
      (node (ref "JP5") (pin "28") (pinfunction "28_28") (pintype "passive"))
      (node (ref "PGA257") (pin "156") (pinfunction "156_156") (pintype "bidirectional"))
    )
    (net (code "157") (name "157") (class "Default")
      (node (ref "JP5") (pin "29") (pinfunction "29_29") (pintype "passive"))
      (node (ref "PGA257") (pin "157") (pinfunction "157_157") (pintype "bidirectional"))
    )
    (net (code "158") (name "158") (class "Default")
      (node (ref "JP5") (pin "30") (pinfunction "30_30") (pintype "passive"))
      (node (ref "PGA257") (pin "158") (pinfunction "158_158") (pintype "bidirectional"))
    )
    (net (code "159") (name "159") (class "Default")
      (node (ref "JP5") (pin "31") (pinfunction "31_31") (pintype "passive"))
      (node (ref "PGA257") (pin "159") (pinfunction "159_159") (pintype "bidirectional"))
    )
    (net (code "160") (name "160") (class "Default")
      (node (ref "JP5") (pin "32") (pinfunction "32_32") (pintype "passive"))
      (node (ref "PGA257") (pin "160") (pinfunction "160_160") (pintype "bidirectional"))
    )
    (net (code "161") (name "161") (class "Default")
      (node (ref "JP6") (pin "1") (pinfunction "1_1") (pintype "passive"))
      (node (ref "PGA257") (pin "161") (pinfunction "161_161") (pintype "bidirectional"))
    )
    (net (code "162") (name "162") (class "Default")
      (node (ref "JP6") (pin "2") (pinfunction "2_2") (pintype "passive"))
      (node (ref "PGA257") (pin "162") (pinfunction "162_162") (pintype "bidirectional"))
    )
    (net (code "163") (name "163") (class "Default")
      (node (ref "JP6") (pin "3") (pinfunction "3_3") (pintype "passive"))
      (node (ref "PGA257") (pin "163") (pinfunction "163_163") (pintype "bidirectional"))
    )
    (net (code "164") (name "164") (class "Default")
      (node (ref "JP6") (pin "4") (pinfunction "4_4") (pintype "passive"))
      (node (ref "PGA257") (pin "164") (pinfunction "164_164") (pintype "bidirectional"))
    )
    (net (code "165") (name "165") (class "Default")
      (node (ref "JP6") (pin "5") (pinfunction "5_5") (pintype "passive"))
      (node (ref "PGA257") (pin "165") (pinfunction "165_165") (pintype "bidirectional"))
    )
    (net (code "166") (name "166") (class "Default")
      (node (ref "JP6") (pin "6") (pinfunction "6_6") (pintype "passive"))
      (node (ref "PGA257") (pin "166") (pinfunction "166_166") (pintype "bidirectional"))
    )
    (net (code "167") (name "167") (class "Default")
      (node (ref "JP6") (pin "7") (pinfunction "7_7") (pintype "passive"))
      (node (ref "PGA257") (pin "167") (pinfunction "167_167") (pintype "bidirectional"))
    )
    (net (code "168") (name "168") (class "Default")
      (node (ref "JP6") (pin "8") (pinfunction "8_8") (pintype "passive"))
      (node (ref "PGA257") (pin "168") (pinfunction "168_168") (pintype "bidirectional"))
    )
    (net (code "169") (name "169") (class "Default")
      (node (ref "JP6") (pin "9") (pinfunction "9_9") (pintype "passive"))
      (node (ref "PGA257") (pin "169") (pinfunction "169_169") (pintype "bidirectional"))
    )
    (net (code "170") (name "170") (class "Default")
      (node (ref "JP6") (pin "10") (pinfunction "10_10") (pintype "passive"))
      (node (ref "PGA257") (pin "170") (pinfunction "170_170") (pintype "bidirectional"))
    )
    (net (code "171") (name "171") (class "Default")
      (node (ref "JP6") (pin "11") (pinfunction "11_11") (pintype "passive"))
      (node (ref "PGA257") (pin "171") (pinfunction "171_171") (pintype "bidirectional"))
    )
    (net (code "172") (name "172") (class "Default")
      (node (ref "JP6") (pin "12") (pinfunction "12_12") (pintype "passive"))
      (node (ref "PGA257") (pin "172") (pinfunction "172_172") (pintype "bidirectional"))
    )
    (net (code "173") (name "173") (class "Default")
      (node (ref "JP6") (pin "13") (pinfunction "13_13") (pintype "passive"))
      (node (ref "PGA257") (pin "173") (pinfunction "173_173") (pintype "bidirectional"))
    )
    (net (code "174") (name "174") (class "Default")
      (node (ref "JP6") (pin "14") (pinfunction "14_14") (pintype "passive"))
      (node (ref "PGA257") (pin "174") (pinfunction "174_174") (pintype "bidirectional"))
    )
    (net (code "175") (name "175") (class "Default")
      (node (ref "JP6") (pin "15") (pinfunction "15_15") (pintype "passive"))
      (node (ref "PGA257") (pin "175") (pinfunction "175_175") (pintype "bidirectional"))
    )
    (net (code "176") (name "176") (class "Default")
      (node (ref "JP6") (pin "16") (pinfunction "16_16") (pintype "passive"))
      (node (ref "PGA257") (pin "176") (pinfunction "176_176") (pintype "bidirectional"))
    )
    (net (code "177") (name "177") (class "Default")
      (node (ref "JP6") (pin "17") (pinfunction "17_17") (pintype "passive"))
      (node (ref "PGA257") (pin "177") (pinfunction "177_177") (pintype "bidirectional"))
    )
    (net (code "178") (name "178") (class "Default")
      (node (ref "JP6") (pin "18") (pinfunction "18_18") (pintype "passive"))
      (node (ref "PGA257") (pin "178") (pinfunction "178_178") (pintype "bidirectional"))
    )
    (net (code "179") (name "179") (class "Default")
      (node (ref "JP6") (pin "19") (pinfunction "19_19") (pintype "passive"))
      (node (ref "PGA257") (pin "179") (pinfunction "179_179") (pintype "bidirectional"))
    )
    (net (code "180") (name "180") (class "Default")
      (node (ref "JP6") (pin "20") (pinfunction "20_20") (pintype "passive"))
      (node (ref "PGA257") (pin "180") (pinfunction "180_180") (pintype "bidirectional"))
    )
    (net (code "181") (name "181") (class "Default")
      (node (ref "JP6") (pin "21") (pinfunction "21_21") (pintype "passive"))
      (node (ref "PGA257") (pin "181") (pinfunction "181_181") (pintype "bidirectional"))
    )
    (net (code "182") (name "182") (class "Default")
      (node (ref "JP6") (pin "22") (pinfunction "22_22") (pintype "passive"))
      (node (ref "PGA257") (pin "182") (pinfunction "182_182") (pintype "bidirectional"))
    )
    (net (code "183") (name "183") (class "Default")
      (node (ref "JP6") (pin "23") (pinfunction "23_23") (pintype "passive"))
      (node (ref "PGA257") (pin "183") (pinfunction "183_183") (pintype "bidirectional"))
    )
    (net (code "184") (name "184") (class "Default")
      (node (ref "JP6") (pin "24") (pinfunction "24_24") (pintype "passive"))
      (node (ref "PGA257") (pin "184") (pinfunction "184_184") (pintype "bidirectional"))
    )
    (net (code "185") (name "185") (class "Default")
      (node (ref "JP6") (pin "25") (pinfunction "25_25") (pintype "passive"))
      (node (ref "PGA257") (pin "185") (pinfunction "185_185") (pintype "bidirectional"))
    )
    (net (code "186") (name "186") (class "Default")
      (node (ref "JP6") (pin "26") (pinfunction "26_26") (pintype "passive"))
      (node (ref "PGA257") (pin "186") (pinfunction "186_186") (pintype "bidirectional"))
    )
    (net (code "187") (name "187") (class "Default")
      (node (ref "JP6") (pin "27") (pinfunction "27_27") (pintype "passive"))
      (node (ref "PGA257") (pin "187") (pinfunction "187_187") (pintype "bidirectional"))
    )
    (net (code "188") (name "188") (class "Default")
      (node (ref "JP6") (pin "28") (pinfunction "28_28") (pintype "passive"))
      (node (ref "PGA257") (pin "188") (pinfunction "188_188") (pintype "bidirectional"))
    )
    (net (code "189") (name "189") (class "Default")
      (node (ref "JP6") (pin "29") (pinfunction "29_29") (pintype "passive"))
      (node (ref "PGA257") (pin "189") (pinfunction "189_189") (pintype "bidirectional"))
    )
    (net (code "190") (name "190") (class "Default")
      (node (ref "JP6") (pin "30") (pinfunction "30_30") (pintype "passive"))
      (node (ref "PGA257") (pin "190") (pinfunction "190_190") (pintype "bidirectional"))
    )
    (net (code "191") (name "191") (class "Default")
      (node (ref "JP6") (pin "31") (pinfunction "31_31") (pintype "passive"))
      (node (ref "PGA257") (pin "191") (pinfunction "191_191") (pintype "bidirectional"))
    )
    (net (code "192") (name "192") (class "Default")
      (node (ref "JP6") (pin "32") (pinfunction "32_32") (pintype "passive"))
      (node (ref "PGA257") (pin "192") (pinfunction "192_192") (pintype "bidirectional"))
    )
    (net (code "193") (name "193") (class "Default")
      (node (ref "JP7") (pin "1") (pinfunction "1_1") (pintype "passive"))
      (node (ref "PGA257") (pin "193") (pinfunction "193_193") (pintype "bidirectional"))
    )
    (net (code "194") (name "194") (class "Default")
      (node (ref "JP7") (pin "2") (pinfunction "2_2") (pintype "passive"))
      (node (ref "PGA257") (pin "194") (pinfunction "194_194") (pintype "bidirectional"))
    )
    (net (code "195") (name "195") (class "Default")
      (node (ref "JP7") (pin "3") (pinfunction "3_3") (pintype "passive"))
      (node (ref "PGA257") (pin "195") (pinfunction "195_195") (pintype "bidirectional"))
    )
    (net (code "196") (name "196") (class "Default")
      (node (ref "JP7") (pin "4") (pinfunction "4_4") (pintype "passive"))
      (node (ref "PGA257") (pin "196") (pinfunction "196_196") (pintype "bidirectional"))
    )
    (net (code "197") (name "197") (class "Default")
      (node (ref "JP7") (pin "5") (pinfunction "5_5") (pintype "passive"))
      (node (ref "PGA257") (pin "197") (pinfunction "197_197") (pintype "bidirectional"))
    )
    (net (code "198") (name "198") (class "Default")
      (node (ref "JP7") (pin "6") (pinfunction "6_6") (pintype "passive"))
      (node (ref "PGA257") (pin "198") (pinfunction "198_198") (pintype "bidirectional"))
    )
    (net (code "199") (name "199") (class "Default")
      (node (ref "JP7") (pin "7") (pinfunction "7_7") (pintype "passive"))
      (node (ref "PGA257") (pin "199") (pinfunction "199_199") (pintype "bidirectional"))
    )
    (net (code "200") (name "200") (class "Default")
      (node (ref "JP7") (pin "8") (pinfunction "8_8") (pintype "passive"))
      (node (ref "PGA257") (pin "200") (pinfunction "200_200") (pintype "bidirectional"))
    )
    (net (code "201") (name "201") (class "Default")
      (node (ref "JP7") (pin "9") (pinfunction "9_9") (pintype "passive"))
      (node (ref "PGA257") (pin "201") (pinfunction "201_201") (pintype "bidirectional"))
    )
    (net (code "202") (name "202") (class "Default")
      (node (ref "JP7") (pin "10") (pinfunction "10_10") (pintype "passive"))
      (node (ref "PGA257") (pin "202") (pinfunction "202_202") (pintype "bidirectional"))
    )
    (net (code "203") (name "203") (class "Default")
      (node (ref "JP7") (pin "11") (pinfunction "11_11") (pintype "passive"))
      (node (ref "PGA257") (pin "203") (pinfunction "203_203") (pintype "bidirectional"))
    )
    (net (code "204") (name "204") (class "Default")
      (node (ref "JP7") (pin "12") (pinfunction "12_12") (pintype "passive"))
      (node (ref "PGA257") (pin "204") (pinfunction "204_204") (pintype "bidirectional"))
    )
    (net (code "205") (name "205") (class "Default")
      (node (ref "JP7") (pin "13") (pinfunction "13_13") (pintype "passive"))
      (node (ref "PGA257") (pin "205") (pinfunction "205_205") (pintype "bidirectional"))
    )
    (net (code "206") (name "206") (class "Default")
      (node (ref "JP7") (pin "14") (pinfunction "14_14") (pintype "passive"))
      (node (ref "PGA257") (pin "206") (pinfunction "206_206") (pintype "bidirectional"))
    )
    (net (code "207") (name "207") (class "Default")
      (node (ref "JP7") (pin "15") (pinfunction "15_15") (pintype "passive"))
      (node (ref "PGA257") (pin "207") (pinfunction "207_207") (pintype "bidirectional"))
    )
    (net (code "208") (name "208") (class "Default")
      (node (ref "JP7") (pin "16") (pinfunction "16_16") (pintype "passive"))
      (node (ref "PGA257") (pin "208") (pinfunction "208_208") (pintype "bidirectional"))
    )
    (net (code "209") (name "209") (class "Default")
      (node (ref "JP7") (pin "17") (pinfunction "17_17") (pintype "passive"))
      (node (ref "PGA257") (pin "209") (pinfunction "209_209") (pintype "bidirectional"))
    )
    (net (code "210") (name "210") (class "Default")
      (node (ref "JP7") (pin "18") (pinfunction "18_18") (pintype "passive"))
      (node (ref "PGA257") (pin "210") (pinfunction "210_210") (pintype "bidirectional"))
    )
    (net (code "211") (name "211") (class "Default")
      (node (ref "JP7") (pin "19") (pinfunction "19_19") (pintype "passive"))
      (node (ref "PGA257") (pin "211") (pinfunction "211_211") (pintype "bidirectional"))
    )
    (net (code "212") (name "212") (class "Default")
      (node (ref "JP7") (pin "20") (pinfunction "20_20") (pintype "passive"))
      (node (ref "PGA257") (pin "212") (pinfunction "212_212") (pintype "bidirectional"))
    )
    (net (code "213") (name "213") (class "Default")
      (node (ref "JP7") (pin "21") (pinfunction "21_21") (pintype "passive"))
      (node (ref "PGA257") (pin "213") (pinfunction "213_213") (pintype "bidirectional"))
    )
    (net (code "214") (name "214") (class "Default")
      (node (ref "JP7") (pin "22") (pinfunction "22_22") (pintype "passive"))
      (node (ref "PGA257") (pin "214") (pinfunction "214_214") (pintype "bidirectional"))
    )
    (net (code "215") (name "215") (class "Default")
      (node (ref "JP7") (pin "23") (pinfunction "23_23") (pintype "passive"))
      (node (ref "PGA257") (pin "215") (pinfunction "215_215") (pintype "bidirectional"))
    )
    (net (code "216") (name "216") (class "Default")
      (node (ref "JP7") (pin "24") (pinfunction "24_24") (pintype "passive"))
      (node (ref "PGA257") (pin "216") (pinfunction "216_216") (pintype "bidirectional"))
    )
    (net (code "217") (name "217") (class "Default")
      (node (ref "JP7") (pin "25") (pinfunction "25_25") (pintype "passive"))
      (node (ref "PGA257") (pin "217") (pinfunction "217_217") (pintype "bidirectional"))
    )
    (net (code "218") (name "218") (class "Default")
      (node (ref "JP7") (pin "26") (pinfunction "26_26") (pintype "passive"))
      (node (ref "PGA257") (pin "218") (pinfunction "218_218") (pintype "bidirectional"))
    )
    (net (code "219") (name "219") (class "Default")
      (node (ref "JP7") (pin "27") (pinfunction "27_27") (pintype "passive"))
      (node (ref "PGA257") (pin "219") (pinfunction "219_219") (pintype "bidirectional"))
    )
    (net (code "220") (name "220") (class "Default")
      (node (ref "JP7") (pin "28") (pinfunction "28_28") (pintype "passive"))
      (node (ref "PGA257") (pin "220") (pinfunction "220_220") (pintype "bidirectional"))
    )
    (net (code "221") (name "221") (class "Default")
      (node (ref "JP7") (pin "29") (pinfunction "29_29") (pintype "passive"))
      (node (ref "PGA257") (pin "221") (pinfunction "221_221") (pintype "bidirectional"))
    )
    (net (code "222") (name "222") (class "Default")
      (node (ref "JP7") (pin "30") (pinfunction "30_30") (pintype "passive"))
      (node (ref "PGA257") (pin "222") (pinfunction "222_222") (pintype "bidirectional"))
    )
    (net (code "223") (name "223") (class "Default")
      (node (ref "JP7") (pin "31") (pinfunction "31_31") (pintype "passive"))
      (node (ref "PGA257") (pin "223") (pinfunction "223_223") (pintype "bidirectional"))
    )
    (net (code "224") (name "224") (class "Default")
      (node (ref "JP7") (pin "32") (pinfunction "32_32") (pintype "passive"))
      (node (ref "PGA257") (pin "224") (pinfunction "224_224") (pintype "bidirectional"))
    )
    (net (code "225") (name "225") (class "Default")
      (node (ref "JP8") (pin "1") (pinfunction "1_1") (pintype "passive"))
      (node (ref "PGA257") (pin "225") (pinfunction "225_225") (pintype "bidirectional"))
    )
    (net (code "226") (name "226") (class "Default")
      (node (ref "JP8") (pin "2") (pinfunction "2_2") (pintype "passive"))
      (node (ref "PGA257") (pin "226") (pinfunction "226_226") (pintype "bidirectional"))
    )
    (net (code "227") (name "227") (class "Default")
      (node (ref "JP8") (pin "3") (pinfunction "3_3") (pintype "passive"))
      (node (ref "PGA257") (pin "227") (pinfunction "227_227") (pintype "bidirectional"))
    )
    (net (code "228") (name "228") (class "Default")
      (node (ref "JP8") (pin "4") (pinfunction "4_4") (pintype "passive"))
      (node (ref "PGA257") (pin "228") (pinfunction "228_228") (pintype "bidirectional"))
    )
    (net (code "229") (name "229") (class "Default")
      (node (ref "JP8") (pin "5") (pinfunction "5_5") (pintype "passive"))
      (node (ref "PGA257") (pin "229") (pinfunction "229_229") (pintype "bidirectional"))
    )
    (net (code "230") (name "230") (class "Default")
      (node (ref "JP8") (pin "6") (pinfunction "6_6") (pintype "passive"))
      (node (ref "PGA257") (pin "230") (pinfunction "230_230") (pintype "bidirectional"))
    )
    (net (code "231") (name "231") (class "Default")
      (node (ref "JP8") (pin "7") (pinfunction "7_7") (pintype "passive"))
      (node (ref "PGA257") (pin "231") (pinfunction "231_231") (pintype "bidirectional"))
    )
    (net (code "232") (name "232") (class "Default")
      (node (ref "JP8") (pin "8") (pinfunction "8_8") (pintype "passive"))
      (node (ref "PGA257") (pin "232") (pinfunction "232_232") (pintype "bidirectional"))
    )
    (net (code "233") (name "233") (class "Default")
      (node (ref "JP8") (pin "9") (pinfunction "9_9") (pintype "passive"))
      (node (ref "PGA257") (pin "233") (pinfunction "233_233") (pintype "bidirectional"))
    )
    (net (code "234") (name "234") (class "Default")
      (node (ref "JP8") (pin "10") (pinfunction "10_10") (pintype "passive"))
      (node (ref "PGA257") (pin "234") (pinfunction "234_234") (pintype "bidirectional"))
    )
    (net (code "235") (name "235") (class "Default")
      (node (ref "JP8") (pin "11") (pinfunction "11_11") (pintype "passive"))
      (node (ref "PGA257") (pin "235") (pinfunction "235_235") (pintype "bidirectional"))
    )
    (net (code "236") (name "236") (class "Default")
      (node (ref "JP8") (pin "12") (pinfunction "12_12") (pintype "passive"))
      (node (ref "PGA257") (pin "236") (pinfunction "236_236") (pintype "bidirectional"))
    )
    (net (code "237") (name "237") (class "Default")
      (node (ref "JP8") (pin "13") (pinfunction "13_13") (pintype "passive"))
      (node (ref "PGA257") (pin "237") (pinfunction "237_237") (pintype "bidirectional"))
    )
    (net (code "238") (name "238") (class "Default")
      (node (ref "JP8") (pin "14") (pinfunction "14_14") (pintype "passive"))
      (node (ref "PGA257") (pin "238") (pinfunction "238_238") (pintype "bidirectional"))
    )
    (net (code "239") (name "239") (class "Default")
      (node (ref "JP8") (pin "15") (pinfunction "15_15") (pintype "passive"))
      (node (ref "PGA257") (pin "239") (pinfunction "239_239") (pintype "bidirectional"))
    )
    (net (code "240") (name "240") (class "Default")
      (node (ref "JP8") (pin "16") (pinfunction "16_16") (pintype "passive"))
      (node (ref "PGA257") (pin "240") (pinfunction "240_240") (pintype "bidirectional"))
    )
    (net (code "241") (name "241") (class "Default")
      (node (ref "JP8") (pin "17") (pinfunction "17_17") (pintype "passive"))
      (node (ref "PGA257") (pin "241") (pinfunction "241_241") (pintype "bidirectional"))
    )
    (net (code "242") (name "242") (class "Default")
      (node (ref "JP8") (pin "18") (pinfunction "18_18") (pintype "passive"))
      (node (ref "PGA257") (pin "242") (pinfunction "242_242") (pintype "bidirectional"))
    )
    (net (code "243") (name "243") (class "Default")
      (node (ref "JP8") (pin "19") (pinfunction "19_19") (pintype "passive"))
      (node (ref "PGA257") (pin "243") (pinfunction "243_243") (pintype "bidirectional"))
    )
    (net (code "244") (name "244") (class "Default")
      (node (ref "JP8") (pin "20") (pinfunction "20_20") (pintype "passive"))
      (node (ref "PGA257") (pin "244") (pinfunction "244_244") (pintype "bidirectional"))
    )
    (net (code "245") (name "245") (class "Default")
      (node (ref "JP8") (pin "21") (pinfunction "21_21") (pintype "passive"))
      (node (ref "PGA257") (pin "245") (pinfunction "245_245") (pintype "bidirectional"))
    )
    (net (code "246") (name "246") (class "Default")
      (node (ref "JP8") (pin "22") (pinfunction "22_22") (pintype "passive"))
      (node (ref "PGA257") (pin "246") (pinfunction "246_246") (pintype "bidirectional"))
    )
    (net (code "247") (name "247") (class "Default")
      (node (ref "JP8") (pin "23") (pinfunction "23_23") (pintype "passive"))
      (node (ref "PGA257") (pin "247") (pinfunction "247_247") (pintype "bidirectional"))
    )
    (net (code "248") (name "248") (class "Default")
      (node (ref "JP8") (pin "24") (pinfunction "24_24") (pintype "passive"))
      (node (ref "PGA257") (pin "248") (pinfunction "248_248") (pintype "bidirectional"))
    )
    (net (code "249") (name "249") (class "Default")
      (node (ref "JP8") (pin "25") (pinfunction "25_25") (pintype "passive"))
      (node (ref "PGA257") (pin "249") (pinfunction "249_249") (pintype "bidirectional"))
    )
    (net (code "250") (name "250") (class "Default")
      (node (ref "JP8") (pin "26") (pinfunction "26_26") (pintype "passive"))
      (node (ref "PGA257") (pin "250") (pinfunction "250_250") (pintype "bidirectional"))
    )
    (net (code "251") (name "251") (class "Default")
      (node (ref "JP8") (pin "27") (pinfunction "27_27") (pintype "passive"))
      (node (ref "PGA257") (pin "251") (pinfunction "251_251") (pintype "bidirectional"))
    )
    (net (code "252") (name "252") (class "Default")
      (node (ref "JP8") (pin "28") (pinfunction "28_28") (pintype "passive"))
      (node (ref "PGA257") (pin "252") (pinfunction "252_252") (pintype "bidirectional"))
    )
    (net (code "253") (name "253") (class "Default")
      (node (ref "JP8") (pin "29") (pinfunction "29_29") (pintype "passive"))
      (node (ref "PGA257") (pin "253") (pinfunction "253_253") (pintype "bidirectional"))
    )
    (net (code "254") (name "254") (class "Default")
      (node (ref "JP8") (pin "30") (pinfunction "30_30") (pintype "passive"))
      (node (ref "PGA257") (pin "254") (pinfunction "254_254") (pintype "bidirectional"))
    )
    (net (code "255") (name "255") (class "Default")
      (node (ref "JP8") (pin "31") (pinfunction "31_31") (pintype "passive"))
      (node (ref "PGA257") (pin "255") (pinfunction "255_255") (pintype "bidirectional"))
    )
    (net (code "256") (name "256") (class "Default")
      (node (ref "JP8") (pin "32") (pinfunction "32_32") (pintype "passive"))
      (node (ref "PGA257") (pin "256") (pinfunction "256_256") (pintype "bidirectional"))
    )
    (net (code "257") (name "257") (class "Default")
      (node (ref "PGA257") (pin "257") (pinfunction "257_257") (pintype "bidirectional"))
    )
  )
)
